# RaduProiectFinal_v18.net
KiCad netlist of a schematic drawn in EAGLE
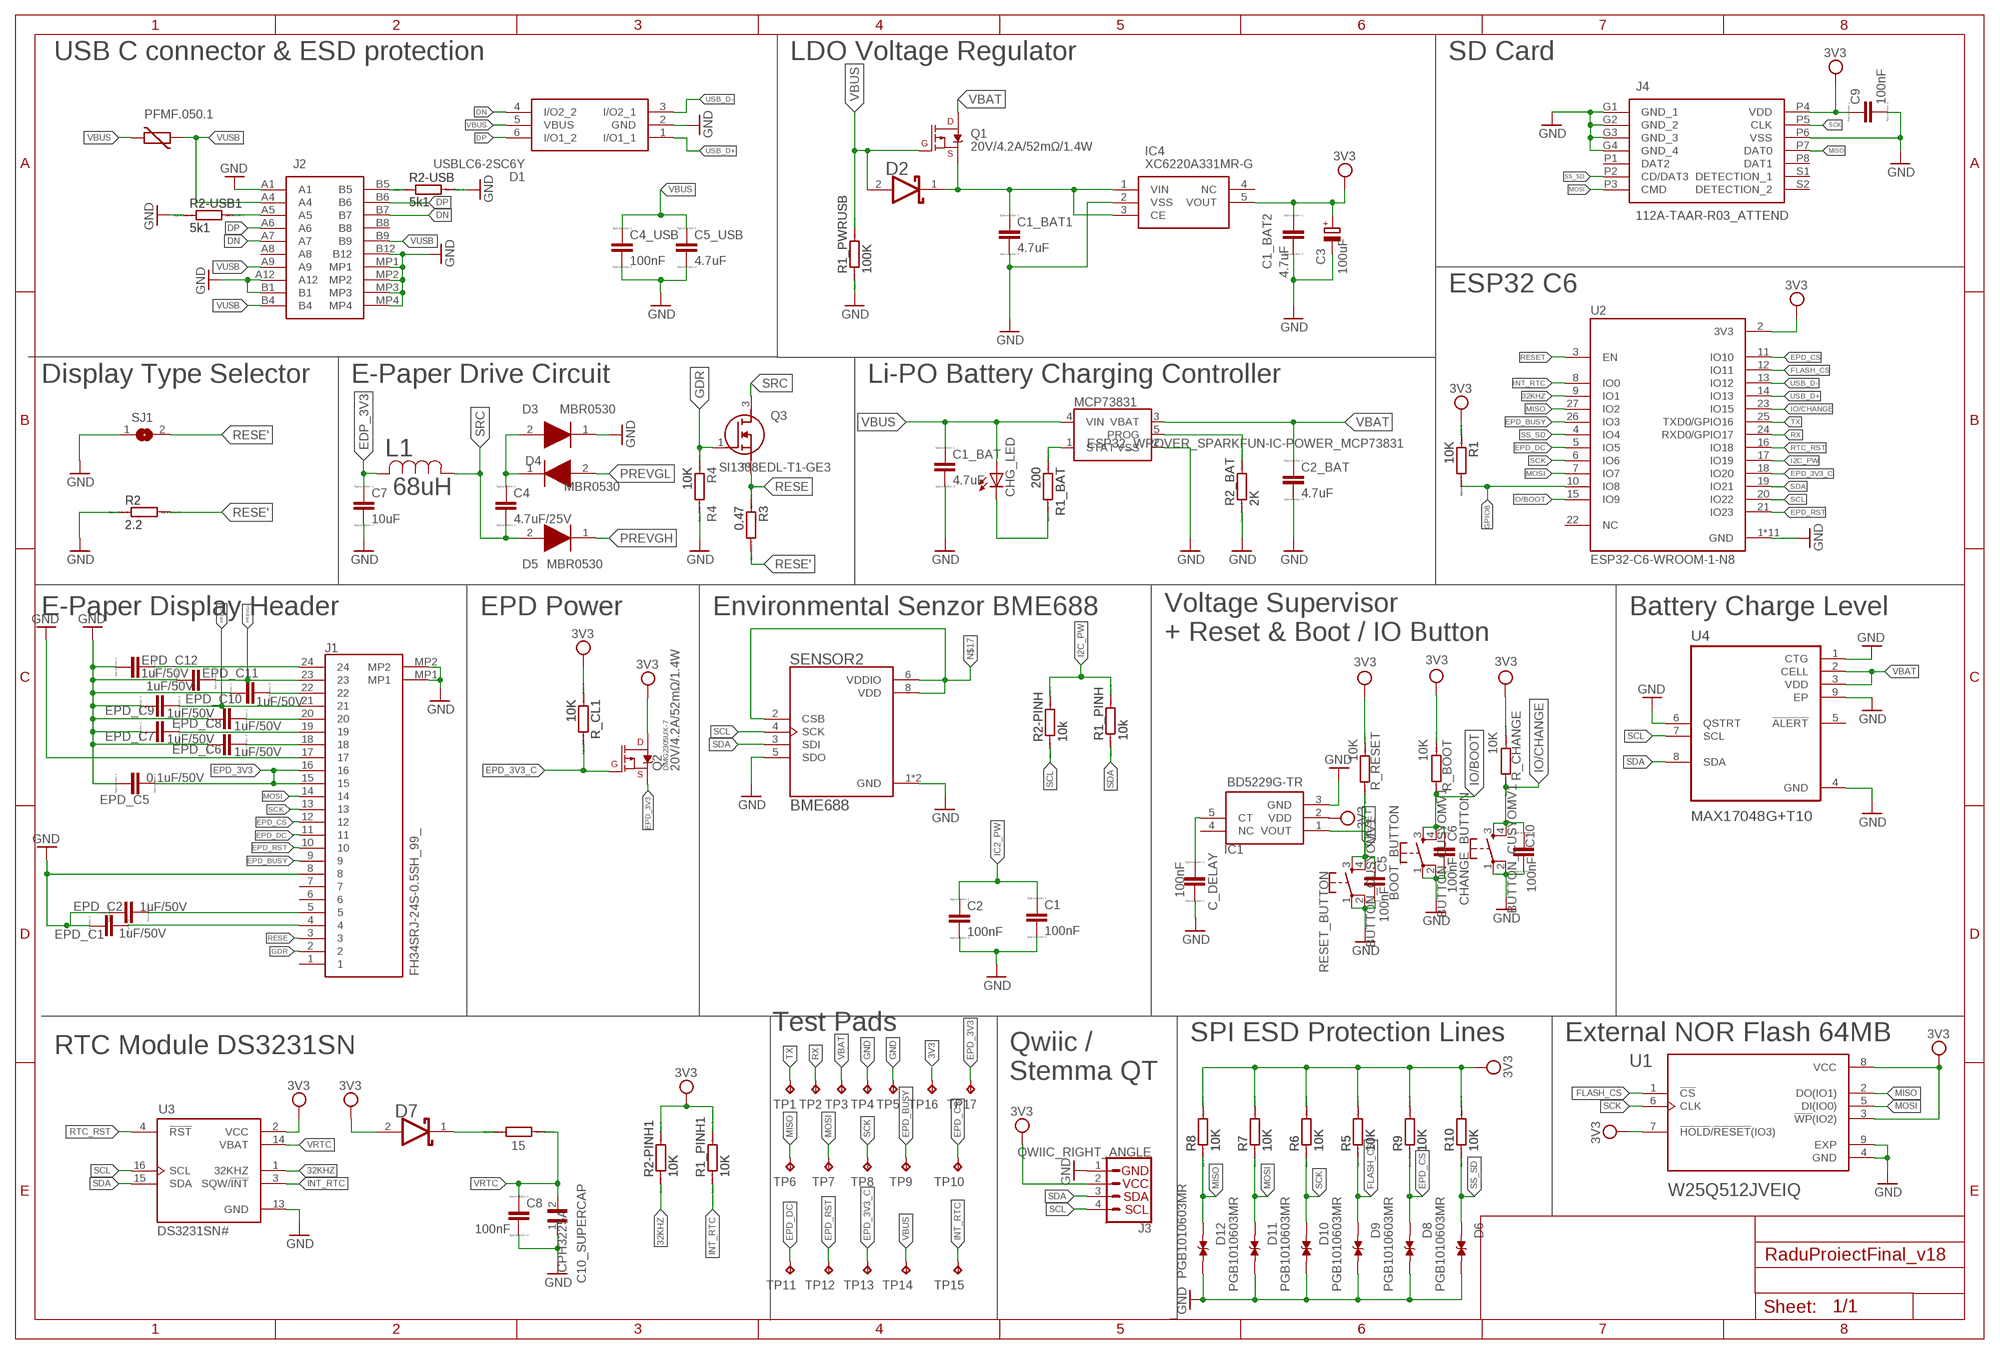
[diagram p0: schematic, sheet 1]

(export (version "E")
  (design (tool "Eeschema 10.0.6"))
  (components
    (comp (ref "BOOT_BUTTON")
      (value "BUTTON_CUSYOMV1")
      (footprint "eagle-import:MYBUTTON")
      (libsource (lib "eagle-import") (part "BUTTON_CUSYOMV1"))
    )
    (comp (ref "C1")
      (value "100nF")
      (footprint "eagle-import:ESP32_WROVER_EAGLE-LTSPICE_C0402")
      (libsource (lib "eagle-import") (part "ESP32_WROVER_EAGLE-LTSPICE_CC0402"))
    )
    (comp (ref "C1_BAT")
      (value "4.7uF")
      (footprint "eagle-import:ESP32_WROVER_EAGLE-LTSPICE_C0402")
      (libsource (lib "eagle-import") (part "ESP32_WROVER_EAGLE-LTSPICE_CC0402"))
    )
    (comp (ref "C1_BAT1")
      (value "4.7uF")
      (footprint "eagle-import:ESP32_WROVER_EAGLE-LTSPICE_C0402")
      (libsource (lib "eagle-import") (part "ESP32_WROVER_EAGLE-LTSPICE_CC0402"))
    )
    (comp (ref "C1_BAT2")
      (value "4.7uF")
      (footprint "eagle-import:ESP32_WROVER_EAGLE-LTSPICE_C0402")
      (libsource (lib "eagle-import") (part "ESP32_WROVER_EAGLE-LTSPICE_CC0402"))
    )
    (comp (ref "C2")
      (value "100nF")
      (footprint "eagle-import:ESP32_WROVER_EAGLE-LTSPICE_C0402")
      (libsource (lib "eagle-import") (part "ESP32_WROVER_EAGLE-LTSPICE_CC0402"))
    )
    (comp (ref "C2_BAT")
      (value "4.7uF")
      (footprint "eagle-import:ESP32_WROVER_EAGLE-LTSPICE_C0402")
      (libsource (lib "eagle-import") (part "ESP32_WROVER_EAGLE-LTSPICE_CC0402"))
    )
    (comp (ref "C3")
      (value "100uF")
      (footprint "eagle-import:RCL_CT3528")
      (libsource (lib "eagle-import") (part "RCL_CPOL-EUCT3528"))
    )
    (comp (ref "C4")
      (value "4.7uF/25V")
      (footprint "eagle-import:ESP32_WROVER_EAGLE-LTSPICE_C0402")
      (libsource (lib "eagle-import") (part "ESP32_WROVER_EAGLE-LTSPICE_CC0402"))
    )
    (comp (ref "C4_USB")
      (value "100nF")
      (footprint "eagle-import:ESP32_WROVER_EAGLE-LTSPICE_C0402")
      (libsource (lib "eagle-import") (part "ESP32_WROVER_EAGLE-LTSPICE_CC0402"))
    )
    (comp (ref "C5")
      (value "100nF")
      (footprint "eagle-import:EAGLE-LTSPICE_C0402")
      (libsource (lib "eagle-import") (part "EAGLE-LTSPICE_CC0402"))
    )
    (comp (ref "C5_USB")
      (value "4.7uF")
      (footprint "eagle-import:ESP32_WROVER_EAGLE-LTSPICE_C0402")
      (libsource (lib "eagle-import") (part "ESP32_WROVER_EAGLE-LTSPICE_CC0402"))
    )
    (comp (ref "C6")
      (value "100nF")
      (footprint "eagle-import:EAGLE-LTSPICE_C0402")
      (libsource (lib "eagle-import") (part "EAGLE-LTSPICE_CC0402"))
    )
    (comp (ref "C7")
      (value "10uF")
      (footprint "eagle-import:ESP32_WROVER_EAGLE-LTSPICE_C0402")
      (libsource (lib "eagle-import") (part "ESP32_WROVER_EAGLE-LTSPICE_CC0402"))
    )
    (comp (ref "C8")
      (value "100nF")
      (footprint "eagle-import:ESP32_WROVER_EAGLE-LTSPICE_C0402")
      (libsource (lib "eagle-import") (part "ESP32_WROVER_EAGLE-LTSPICE_CC0402"))
    )
    (comp (ref "C9")
      (value "100nF")
      (footprint "eagle-import:ESP32_WROVER_EAGLE-LTSPICE_C0402")
      (libsource (lib "eagle-import") (part "ESP32_WROVER_EAGLE-LTSPICE_CC0402"))
    )
    (comp (ref "C10")
      (value "100nF")
      (footprint "eagle-import:EAGLE-LTSPICE_C0402")
      (libsource (lib "eagle-import") (part "EAGLE-LTSPICE_CC0402"))
    )
    (comp (ref "C10_SUPERCAP")
      (value "CPH3225A")
      (footprint "eagle-import:CAPCP3225X100N")
      (fields (field (name "MF") "Seiko Instruments"))
      (libsource (lib "eagle-import") (part "CPH3225A"))
    )
    (comp (ref "CHANGE_BUTTON")
      (value "BUTTON_CUSYOMV1")
      (footprint "eagle-import:MYBUTTON")
      (libsource (lib "eagle-import") (part "BUTTON_CUSYOMV1"))
    )
    (comp (ref "CHG_LED")
      (value "ADAFRUIT_LEDCHIP-LED0603")
      (footprint "eagle-import:ADAFRUIT_CHIP-LED0603")
      (libsource (lib "eagle-import") (part "ADAFRUIT_LEDCHIP-LED0603"))
    )
    (comp (ref "C_DELAY")
      (value "100nF")
      (footprint "eagle-import:ESP32_WROVER_EAGLE-LTSPICE_C0402")
      (libsource (lib "eagle-import") (part "ESP32_WROVER_EAGLE-LTSPICE_CC0402"))
    )
    (comp (ref "D1")
      (value "USBLC6-2SC6Y")
      (footprint "eagle-import:SOT95P280X145-6N")
      (fields (field (name "MF") "STMicroelectronics"))
      (libsource (lib "eagle-import") (part "USBLC6-2SC6Y"))
    )
    (comp (ref "D2")
      (value "ESP32_WROVER_AVX---SD0805S020S1R0_AVX_SD0805S020S1R0_0_0AVX_SD0805S020S1R0_0_0")
      (footprint "eagle-import:ESP32_WROVER_AVX---SD0805S020S1R0_AVX_SD0805S020S1R0_0")
      (fields
        (field (name "DIGIKEY_PART_NUMBER") "478-7800-1-ND")
        (field (name "MF") "AVX")
        (field (name "MOUSER_PART_NUMBER") "581-SD0805S020S1R0")
      )
      (libsource (lib "eagle-import") (part "ESP32_WROVER_AVX---SD0805S020S1R0_AVX_SD0805S020S1R0_0_0AVX_SD0805S020S1R0_0_0"))
    )
    (comp (ref "D3")
      (value "MBR0530")
      (footprint "eagle-import:SOD3716X135N")
      (fields (field (name "MF") "ON Semiconductor"))
      (libsource (lib "eagle-import") (part "MBR0530"))
    )
    (comp (ref "D4")
      (value "MBR0530")
      (footprint "eagle-import:SOD3716X135N")
      (fields (field (name "MF") "ON Semiconductor"))
      (libsource (lib "eagle-import") (part "MBR0530"))
    )
    (comp (ref "D5")
      (value "MBR0530")
      (footprint "eagle-import:SOD3716X135N")
      (fields (field (name "MF") "ON Semiconductor"))
      (libsource (lib "eagle-import") (part "MBR0530"))
    )
    (comp (ref "D6")
      (value "PGB1010603MR")
      (footprint "eagle-import:DIOC1608X36N")
      (fields (field (name "MF") "Littelfuse Inc."))
      (libsource (lib "eagle-import") (part "PGB1010603MR"))
    )
    (comp (ref "D7")
      (value "ESP32_WROVER_AVX---SD0805S020S1R0_AVX_SD0805S020S1R0_0_0AVX_SD0805S020S1R0_0_0")
      (footprint "eagle-import:ESP32_WROVER_AVX---SD0805S020S1R0_AVX_SD0805S020S1R0_0")
      (fields
        (field (name "DIGIKEY_PART_NUMBER") "478-7800-1-ND")
        (field (name "MF") "AVX")
        (field (name "MOUSER_PART_NUMBER") "581-SD0805S020S1R0")
      )
      (libsource (lib "eagle-import") (part "ESP32_WROVER_AVX---SD0805S020S1R0_AVX_SD0805S020S1R0_0_0AVX_SD0805S020S1R0_0_0"))
    )
    (comp (ref "D8")
      (value "PGB1010603MR")
      (footprint "eagle-import:DIOC1608X36N")
      (fields (field (name "MF") "Littelfuse Inc."))
      (libsource (lib "eagle-import") (part "PGB1010603MR"))
    )
    (comp (ref "D9")
      (value "PGB1010603MR")
      (footprint "eagle-import:DIOC1608X36N")
      (fields (field (name "MF") "Littelfuse Inc."))
      (libsource (lib "eagle-import") (part "PGB1010603MR"))
    )
    (comp (ref "D10")
      (value "PGB1010603MR")
      (footprint "eagle-import:DIOC1608X36N")
      (fields (field (name "MF") "Littelfuse Inc."))
      (libsource (lib "eagle-import") (part "PGB1010603MR"))
    )
    (comp (ref "D11")
      (value "PGB1010603MR")
      (footprint "eagle-import:DIOC1608X36N")
      (fields (field (name "MF") "Littelfuse Inc."))
      (libsource (lib "eagle-import") (part "PGB1010603MR"))
    )
    (comp (ref "D12")
      (value "PGB1010603MR")
      (footprint "eagle-import:DIOC1608X36N")
      (fields (field (name "MF") "Littelfuse Inc."))
      (libsource (lib "eagle-import") (part "PGB1010603MR"))
    )
    (comp (ref "EPD_C1")
      (value "1uF/50V")
      (footprint "eagle-import:EAGLE-LTSPICE_C0402")
      (libsource (lib "eagle-import") (part "EAGLE-LTSPICE_CC0402"))
    )
    (comp (ref "EPD_C2")
      (value "1uF/50V")
      (footprint "eagle-import:EAGLE-LTSPICE_C0402")
      (libsource (lib "eagle-import") (part "EAGLE-LTSPICE_CC0402"))
    )
    (comp (ref "EPD_C5")
      (value "0.1uF/50V")
      (footprint "eagle-import:EAGLE-LTSPICE_C0402")
      (libsource (lib "eagle-import") (part "EAGLE-LTSPICE_CC0402"))
    )
    (comp (ref "EPD_C6")
      (value "1uF/50V")
      (footprint "eagle-import:EAGLE-LTSPICE_C0402")
      (libsource (lib "eagle-import") (part "EAGLE-LTSPICE_CC0402"))
    )
    (comp (ref "EPD_C7")
      (value "1uF/50V")
      (footprint "eagle-import:EAGLE-LTSPICE_C0402")
      (libsource (lib "eagle-import") (part "EAGLE-LTSPICE_CC0402"))
    )
    (comp (ref "EPD_C8")
      (value "1uF/50V")
      (footprint "eagle-import:EAGLE-LTSPICE_C0402")
      (libsource (lib "eagle-import") (part "EAGLE-LTSPICE_CC0402"))
    )
    (comp (ref "EPD_C9")
      (value "1uF/50V")
      (footprint "eagle-import:EAGLE-LTSPICE_C0402")
      (libsource (lib "eagle-import") (part "EAGLE-LTSPICE_CC0402"))
    )
    (comp (ref "EPD_C10")
      (value "1uF/50V")
      (footprint "eagle-import:EAGLE-LTSPICE_C0402")
      (libsource (lib "eagle-import") (part "EAGLE-LTSPICE_CC0402"))
    )
    (comp (ref "EPD_C11")
      (value "1uF/50V")
      (footprint "eagle-import:EAGLE-LTSPICE_C0402")
      (libsource (lib "eagle-import") (part "EAGLE-LTSPICE_CC0402"))
    )
    (comp (ref "EPD_C12")
      (value "1uF/50V")
      (footprint "eagle-import:EAGLE-LTSPICE_C0402")
      (libsource (lib "eagle-import") (part "EAGLE-LTSPICE_CC0402"))
    )
    (comp (ref "IC1")
      (value "BD5229G-TR")
      (footprint "eagle-import:SOT95P280X125-5N")
      (fields (field (name "MOUSER_PART_NUMBER") "755-BD5229G-TR"))
      (libsource (lib "eagle-import") (part "BD5229G-TR"))
    )
    (comp (ref "IC4")
      (value "XC6220A331MR-G")
      (footprint "eagle-import:SOT95P280X120-5N")
      (fields (field (name "MOUSER_PART_NUMBER") "865-XC6220A331MR-G"))
      (libsource (lib "eagle-import") (part "XC6220A331MR-G"))
    )
    (comp (ref "J1")
      (value "FH34SRJ-24S-0.5SH_99_")
      (footprint "eagle-import:FH34SRJ24S05SH99")
      (fields
        (field (name "MANUFACTURER_PART_NUMBER") "FH34SRJ-24S-0.5SH(99)")
        (field (name "MOUSER_PART_NUMBER") "798-FH34SRJ24S05SH99")
      )
      (libsource (lib "eagle-import") (part "FH34SRJ-24S-0.5SH_99_"))
    )
    (comp (ref "J2")
      (value "SAMACSYS_PARTS_USB4110-GF-A")
      (footprint "eagle-import:SAMACSYS_PARTS_USB4110GFA")
      (fields
        (field (name "MANUFACTURER_PART_NUMBER") "USB4110-GF-A")
        (field (name "MOUSER_PART_NUMBER") "640-USB4110-GF-A")
      )
      (libsource (lib "eagle-import") (part "SAMACSYS_PARTS_USB4110-GF-A"))
    )
    (comp (ref "J3")
      (value "QWIIC_RIGHT_ANGLE")
      (footprint "eagle-import:JST04_1MM_RA")
      (libsource (lib "eagle-import") (part "QWIIC_CONNECTORJS-1MM"))
    )
    (comp (ref "J4")
      (value "112A-TAAR-R03_ATTEND")
      (footprint "eagle-import:112ATAARR03ATTEND")
      (fields (field (name "MANUFACTURER_PART_NUMBER") "112A-TAAR-R03 ATTEND"))
      (libsource (lib "eagle-import") (part "112A-TAAR-R03_ATTEND"))
    )
    (comp (ref "L1")
      (value "68uH")
      (footprint "eagle-import:IND_4828-WE-TPC_WRE")
      (fields
        (field (name "MANUFACTURER_PART_NUMBER") "744043680")
        (field (name "COPYRIGHT") "Copyright (C) 2024 Ultra Librarian. All rights reserved.")
      )
      (libsource (lib "eagle-import") (part "744043680IND_4828-WE-TPC_WRE"))
    )
    (comp (ref "MCP73831")
      (value "ESP32_WROVER_SPARKFUN-IC-POWER_MCP73831")
      (footprint "eagle-import:ESP32_WROVER_SPARKFUN-IC-POWER_SOT23-5")
      (libsource (lib "eagle-import") (part "ESP32_WROVER_SPARKFUN-IC-POWER_MCP73831"))
    )
    (comp (ref "PFMF.050.1")
      (value "ESP32C6_VARISTORCN1812")
      (footprint "eagle-import:ESP32C6_VARISTOR_CT_CN1812")
      (libsource (lib "eagle-import") (part "ESP32C6_VARISTORCN1812"))
    )
    (comp (ref "Q1")
      (value "20V/4.2A/52mΩ/1.4W")
      (footprint "eagle-import:ESP32_WROVER_SPARKFUN-DISCRETESEMI_SOT23-3")
      (libsource (lib "eagle-import") (part "ESP32_WROVER_SPARKFUN-DISCRETESEMI_MOSFET_PCH-DMG2305UX-7"))
    )
    (comp (ref "Q2")
      (value "20V/4.2A/52mΩ/1.4W")
      (footprint "eagle-import:ESP32_WROVER_SPARKFUN-DISCRETESEMI_SOT23-3")
      (libsource (lib "eagle-import") (part "ESP32_WROVER_SPARKFUN-DISCRETESEMI_MOSFET_PCH-DMG2305UX-7"))
    )
    (comp (ref "Q3")
      (value "SI1308EDL-T1-GE3")
      (footprint "eagle-import:SOT65P210X110-3N")
      (fields (field (name "MF") "Vishay Siliconix"))
      (libsource (lib "eagle-import") (part "SI1308EDL-T1-GE3"))
    )
    (comp (ref "R1")
      (value "10K")
      (footprint "eagle-import:ESP32_WROVER_EAGLE-LTSPICE_R0402")
      (libsource (lib "eagle-import") (part "ESP32_WROVER_EAGLE-LTSPICE_RR0402"))
    )
    (comp (ref "R1_BAT")
      (value "200")
      (footprint "eagle-import:ESP32_WROVER_EAGLE-LTSPICE_R0402")
      (libsource (lib "eagle-import") (part "ESP32_WROVER_EAGLE-LTSPICE_RR0402"))
    )
    (comp (ref "R1_PINH")
      (value "10k")
      (footprint "eagle-import:ESP32_WROVER_EAGLE-LTSPICE_R0402")
      (libsource (lib "eagle-import") (part "ESP32_WROVER_EAGLE-LTSPICE_RR0402"))
    )
    (comp (ref "R1_PINH1")
      (value "10K")
      (footprint "eagle-import:ESP32_WROVER_EAGLE-LTSPICE_R0402")
      (libsource (lib "eagle-import") (part "ESP32_WROVER_EAGLE-LTSPICE_RR0402"))
    )
    (comp (ref "R1_PWRUSB")
      (value "100K")
      (footprint "eagle-import:ESP32_WROVER_EAGLE-LTSPICE_R0402")
      (libsource (lib "eagle-import") (part "ESP32_WROVER_EAGLE-LTSPICE_RR0402"))
    )
    (comp (ref "R2")
      (value "2.2")
      (footprint "eagle-import:ESP32_WROVER_EAGLE-LTSPICE_R0402")
      (libsource (lib "eagle-import") (part "ESP32_WROVER_EAGLE-LTSPICE_RR0402"))
    )
    (comp (ref "R2-PINH")
      (value "10k")
      (footprint "eagle-import:ESP32_WROVER_EAGLE-LTSPICE_R0402")
      (libsource (lib "eagle-import") (part "ESP32_WROVER_EAGLE-LTSPICE_RR0402"))
    )
    (comp (ref "R2-PINH1")
      (value "10K")
      (footprint "eagle-import:ESP32_WROVER_EAGLE-LTSPICE_R0402")
      (libsource (lib "eagle-import") (part "ESP32_WROVER_EAGLE-LTSPICE_RR0402"))
    )
    (comp (ref "R2-USB")
      (value "5k1")
      (footprint "eagle-import:ESP32_WROVER_EAGLE-LTSPICE_R0402")
      (libsource (lib "eagle-import") (part "ESP32_WROVER_EAGLE-LTSPICE_RR0402"))
    )
    (comp (ref "R2-USB1")
      (value "5k1")
      (footprint "eagle-import:ESP32_WROVER_EAGLE-LTSPICE_R0402")
      (libsource (lib "eagle-import") (part "ESP32_WROVER_EAGLE-LTSPICE_RR0402"))
    )
    (comp (ref "R2_BAT")
      (value "2K")
      (footprint "eagle-import:ESP32_WROVER_EAGLE-LTSPICE_R0402")
      (libsource (lib "eagle-import") (part "ESP32_WROVER_EAGLE-LTSPICE_RR0402"))
    )
    (comp (ref "R3")
      (value "0.47")
      (footprint "eagle-import:ESP32_WROVER_EAGLE-LTSPICE_R0402")
      (libsource (lib "eagle-import") (part "ESP32_WROVER_EAGLE-LTSPICE_RR0402"))
    )
    (comp (ref "R4")
      (value "10K")
      (footprint "eagle-import:ESP32_WROVER_EAGLE-LTSPICE_R0402")
      (libsource (lib "eagle-import") (part "ESP32_WROVER_EAGLE-LTSPICE_RR0402"))
    )
    (comp (ref "R5")
      (value "10K")
      (footprint "eagle-import:ESP32_WROVER_EAGLE-LTSPICE_R0402")
      (libsource (lib "eagle-import") (part "ESP32_WROVER_EAGLE-LTSPICE_RR0402"))
    )
    (comp (ref "R6")
      (value "10K")
      (footprint "eagle-import:ESP32_WROVER_EAGLE-LTSPICE_R0402")
      (libsource (lib "eagle-import") (part "ESP32_WROVER_EAGLE-LTSPICE_RR0402"))
    )
    (comp (ref "R7")
      (value "10K")
      (footprint "eagle-import:ESP32_WROVER_EAGLE-LTSPICE_R0402")
      (libsource (lib "eagle-import") (part "ESP32_WROVER_EAGLE-LTSPICE_RR0402"))
    )
    (comp (ref "R8")
      (value "10K")
      (footprint "eagle-import:ESP32_WROVER_EAGLE-LTSPICE_R0402")
      (libsource (lib "eagle-import") (part "ESP32_WROVER_EAGLE-LTSPICE_RR0402"))
    )
    (comp (ref "R9")
      (value "10K")
      (footprint "eagle-import:ESP32_WROVER_EAGLE-LTSPICE_R0402")
      (libsource (lib "eagle-import") (part "ESP32_WROVER_EAGLE-LTSPICE_RR0402"))
    )
    (comp (ref "R10")
      (value "10K")
      (footprint "eagle-import:ESP32_WROVER_EAGLE-LTSPICE_R0402")
      (libsource (lib "eagle-import") (part "ESP32_WROVER_EAGLE-LTSPICE_RR0402"))
    )
    (comp (ref "RESET_BUTTON")
      (value "BUTTON_CUSYOMV1")
      (footprint "eagle-import:MYBUTTON")
      (libsource (lib "eagle-import") (part "BUTTON_CUSYOMV1"))
    )
    (comp (ref "R_BOOT")
      (value "10K")
      (footprint "eagle-import:ESP32_WROVER_EAGLE-LTSPICE_R0402")
      (libsource (lib "eagle-import") (part "ESP32_WROVER_EAGLE-LTSPICE_RR0402"))
    )
    (comp (ref "R_CAPACITOR")
      (value "15")
      (footprint "eagle-import:ESP32_WROVER_EAGLE-LTSPICE_R0402")
      (libsource (lib "eagle-import") (part "ESP32_WROVER_EAGLE-LTSPICE_RR0402"))
    )
    (comp (ref "R_CHANGE")
      (value "10K")
      (footprint "eagle-import:ESP32_WROVER_EAGLE-LTSPICE_R0402")
      (libsource (lib "eagle-import") (part "ESP32_WROVER_EAGLE-LTSPICE_RR0402"))
    )
    (comp (ref "R_CL1")
      (value "10K")
      (footprint "eagle-import:ESP32_WROVER_EAGLE-LTSPICE_R0402")
      (libsource (lib "eagle-import") (part "ESP32_WROVER_EAGLE-LTSPICE_RR0402"))
    )
    (comp (ref "R_RESET")
      (value "10K")
      (footprint "eagle-import:ESP32_WROVER_EAGLE-LTSPICE_R0402")
      (libsource (lib "eagle-import") (part "ESP32_WROVER_EAGLE-LTSPICE_RR0402"))
    )
    (comp (ref "SENSOR2")
      (value "BME688")
      (footprint "eagle-import:ESP32_WROVER_BME680_PSON80P300X300X100-8N")
      (fields (field (name "MF") "Bosch Sensortec") (field (name "MP") "BME680"))
      (libsource (lib "eagle-import") (part "ESP32_WROVER_BME680_BME680"))
    )
    (comp (ref "SJ1") (value "SJ") (footprint "eagle-import:SJ") (libsource (lib "eagle-import") (part "SJ")))
    (comp (ref "TP1")
      (value "TPTP20R")
      (footprint "eagle-import:TP20R")
      (libsource (lib "eagle-import") (part "TPTP20R"))
    )
    (comp (ref "TP2")
      (value "TPTP20R")
      (footprint "eagle-import:TP20R")
      (libsource (lib "eagle-import") (part "TPTP20R"))
    )
    (comp (ref "TP3")
      (value "TPTP20R")
      (footprint "eagle-import:TP20R")
      (libsource (lib "eagle-import") (part "TPTP20R"))
    )
    (comp (ref "TP4")
      (value "TPTP20R")
      (footprint "eagle-import:TP20R")
      (libsource (lib "eagle-import") (part "TPTP20R"))
    )
    (comp (ref "TP5")
      (value "TPTP20R")
      (footprint "eagle-import:TP20R")
      (libsource (lib "eagle-import") (part "TPTP20R"))
    )
    (comp (ref "TP6")
      (value "TPTP20R")
      (footprint "eagle-import:TP20R")
      (libsource (lib "eagle-import") (part "TPTP20R"))
    )
    (comp (ref "TP7")
      (value "TPTP20R")
      (footprint "eagle-import:TP20R")
      (libsource (lib "eagle-import") (part "TPTP20R"))
    )
    (comp (ref "TP8")
      (value "TPTP20R")
      (footprint "eagle-import:TP20R")
      (libsource (lib "eagle-import") (part "TPTP20R"))
    )
    (comp (ref "TP9")
      (value "TPTP20R")
      (footprint "eagle-import:TP20R")
      (libsource (lib "eagle-import") (part "TPTP20R"))
    )
    (comp (ref "TP10")
      (value "TPTP20R")
      (footprint "eagle-import:TP20R")
      (libsource (lib "eagle-import") (part "TPTP20R"))
    )
    (comp (ref "TP11")
      (value "TPTP20R")
      (footprint "eagle-import:TP20R")
      (libsource (lib "eagle-import") (part "TPTP20R"))
    )
    (comp (ref "TP12")
      (value "TPTP20R")
      (footprint "eagle-import:TP20R")
      (libsource (lib "eagle-import") (part "TPTP20R"))
    )
    (comp (ref "TP13")
      (value "TPTP20R")
      (footprint "eagle-import:TP20R")
      (libsource (lib "eagle-import") (part "TPTP20R"))
    )
    (comp (ref "TP14")
      (value "TPTP20R")
      (footprint "eagle-import:TP20R")
      (libsource (lib "eagle-import") (part "TPTP20R"))
    )
    (comp (ref "TP15")
      (value "TPTP20R")
      (footprint "eagle-import:TP20R")
      (libsource (lib "eagle-import") (part "TPTP20R"))
    )
    (comp (ref "TP16")
      (value "TPTP20R")
      (footprint "eagle-import:TP20R")
      (libsource (lib "eagle-import") (part "TPTP20R"))
    )
    (comp (ref "TP17")
      (value "TPTP20R")
      (footprint "eagle-import:TP20R")
      (libsource (lib "eagle-import") (part "TPTP20R"))
    )
    (comp (ref "U1")
      (value "W25Q512JVEIQ")
      (footprint "eagle-import:SON127P600X800X80-9N")
      (fields (field (name "MF") "Winbond Electronics"))
      (libsource (lib "eagle-import") (part "W25Q512JVEIQ"))
    )
    (comp (ref "U2")
      (value "ESP32-C6-WROOM-1-N8")
      (footprint "eagle-import:XCVR_ESP32-C6-WROOM-1-N8")
      (fields (field (name "MF") "Espressif Systems"))
      (libsource (lib "eagle-import") (part "ESP32-C6-WROOM-1-N8"))
    )
    (comp (ref "U3")
      (value "DS3231SN#")
      (footprint "eagle-import:SOIC127P1032X265-16N")
      (fields (field (name "MF") "Analog Devices"))
      (libsource (lib "eagle-import") (part "DS3231SN#"))
    )
    (comp (ref "U4")
      (value "MAX17048G+T10")
      (footprint "eagle-import:SON50P200X200X80-9N")
      (fields (field (name "MF") "Analog Devices"))
      (libsource (lib "eagle-import") (part "MAX17048G+T10"))
    )
  )
  (nets
    (net (code "1") (name "3V3") (class "Default")
      (node (ref "C1_BAT2") (pin "1") (pinfunction "1_1") (pintype "passive"))
      (node (ref "C3") (pin "+") (pinfunction "+_+") (pintype "passive"))
      (node (ref "C9") (pin "1") (pinfunction "1_1") (pintype "passive"))
      (node (ref "D7") (pin "2") (pinfunction "ANODE_2") (pintype "bidirectional"))
      (node (ref "IC4") (pin "5") (pinfunction "VOUT_5") (pintype "bidirectional"))
      (node (ref "J3") (pin "2") (pinfunction "2_2") (pintype "power_in"))
      (node (ref "J4") (pin "P4") (pinfunction "VDD_P4") (pintype "bidirectional"))
      (node (ref "Q2") (pin "3") (pinfunction "D_3") (pintype "bidirectional"))
      (node (ref "R1") (pin "1") (pinfunction "1_1") (pintype "passive"))
      (node (ref "R10") (pin "2") (pinfunction "2_2") (pintype "passive"))
      (node (ref "R1_PINH1") (pin "2") (pinfunction "2_2") (pintype "passive"))
      (node (ref "R2-PINH1") (pin "2") (pinfunction "2_2") (pintype "passive"))
      (node (ref "R5") (pin "2") (pinfunction "2_2") (pintype "passive"))
      (node (ref "R6") (pin "2") (pinfunction "2_2") (pintype "passive"))
      (node (ref "R7") (pin "2") (pinfunction "2_2") (pintype "passive"))
      (node (ref "R8") (pin "2") (pinfunction "2_2") (pintype "passive"))
      (node (ref "R9") (pin "2") (pinfunction "2_2") (pintype "passive"))
      (node (ref "R_BOOT") (pin "2") (pinfunction "2_2") (pintype "passive"))
      (node (ref "R_CHANGE") (pin "2") (pinfunction "2_2") (pintype "passive"))
      (node (ref "R_CL1") (pin "1") (pinfunction "1_1") (pintype "passive"))
      (node (ref "R_RESET") (pin "2") (pinfunction "2_2") (pintype "passive"))
      (node (ref "TP16") (pin "TP") (pinfunction "TP_TP") (pintype "input"))
      (node (ref "U1") (pin "3") (pinfunction "~{WP}(IO2)_3") (pintype "bidirectional"))
      (node (ref "U1") (pin "7") (pinfunction "~{HOLD}/~{RESET}(IO3)_7") (pintype "bidirectional"))
      (node (ref "U1") (pin "8") (pinfunction "VCC_8") (pintype "power_in"))
      (node (ref "U2") (pin "2") (pinfunction "3V3_2") (pintype "power_in"))
      (node (ref "U3") (pin "2") (pinfunction "VCC_2") (pintype "power_in"))
    )
    (net (code "2") (name "32KHZ") (class "Default")
      (node (ref "R2-PINH1") (pin "1") (pinfunction "1_1") (pintype "passive"))
      (node (ref "U2") (pin "9") (pinfunction "IO1_9") (pintype "bidirectional"))
      (node (ref "U3") (pin "1") (pinfunction "32KHZ_1") (pintype "output"))
    )
    (net (code "3") (name "DN") (class "Default")
      (node (ref "D1") (pin "4") (pinfunction "I/O2_2_4") (pintype "bidirectional"))
      (node (ref "J2") (pin "A7") (pinfunction "A7_A7") (pintype "bidirectional"))
      (node (ref "J2") (pin "B7") (pinfunction "B7_B7") (pintype "bidirectional"))
    )
    (net (code "4") (name "DP") (class "Default")
      (node (ref "D1") (pin "6") (pinfunction "I/O1_2_6") (pintype "bidirectional"))
      (node (ref "J2") (pin "A6") (pinfunction "A6_A6") (pintype "bidirectional"))
      (node (ref "J2") (pin "B6") (pinfunction "B6_B6") (pintype "bidirectional"))
    )
    (net (code "5") (name "EDP_3V3") (class "Default")
      (node (ref "C7") (pin "1") (pinfunction "1_1") (pintype "passive"))
      (node (ref "L1") (pin "2") (pinfunction "2_2") (pintype "passive"))
    )
    (net (code "6") (name "EPD_3V3") (class "Default")
      (node (ref "EPD_C5") (pin "2") (pinfunction "2_2") (pintype "passive"))
      (node (ref "J1") (pin "15") (pinfunction "15_15") (pintype "bidirectional"))
      (node (ref "J1") (pin "16") (pinfunction "16_16") (pintype "bidirectional"))
      (node (ref "Q2") (pin "2") (pinfunction "S_2") (pintype "bidirectional"))
      (node (ref "TP17") (pin "TP") (pinfunction "TP_TP") (pintype "input"))
    )
    (net (code "7") (name "EPD_3V3_C") (class "Default")
      (node (ref "Q2") (pin "1") (pinfunction "G_1") (pintype "bidirectional"))
      (node (ref "R_CL1") (pin "2") (pinfunction "2_2") (pintype "passive"))
      (node (ref "TP13") (pin "TP") (pinfunction "TP_TP") (pintype "input"))
      (node (ref "U2") (pin "18") (pinfunction "IO20_18") (pintype "bidirectional"))
    )
    (net (code "8") (name "EPD_BUSY") (class "Default")
      (node (ref "J1") (pin "9") (pinfunction "9_9") (pintype "bidirectional"))
      (node (ref "TP9") (pin "TP") (pinfunction "TP_TP") (pintype "input"))
      (node (ref "U2") (pin "26") (pinfunction "IO3_26") (pintype "bidirectional"))
    )
    (net (code "9") (name "EPD_CS") (class "Default")
      (node (ref "D8") (pin "1") (pinfunction "1_1") (pintype "passive"))
      (node (ref "J1") (pin "12") (pinfunction "12_12") (pintype "bidirectional"))
      (node (ref "R9") (pin "1") (pinfunction "1_1") (pintype "passive"))
      (node (ref "TP10") (pin "TP") (pinfunction "TP_TP") (pintype "input"))
      (node (ref "U2") (pin "11") (pinfunction "IO10_11") (pintype "bidirectional"))
    )
    (net (code "10") (name "EPD_DC") (class "Default")
      (node (ref "J1") (pin "11") (pinfunction "11_11") (pintype "bidirectional"))
      (node (ref "TP11") (pin "TP") (pinfunction "TP_TP") (pintype "input"))
      (node (ref "U2") (pin "5") (pinfunction "IO5_5") (pintype "bidirectional"))
    )
    (net (code "11") (name "EPD_RST") (class "Default")
      (node (ref "J1") (pin "10") (pinfunction "10_10") (pintype "bidirectional"))
      (node (ref "TP12") (pin "TP") (pinfunction "TP_TP") (pintype "input"))
      (node (ref "U2") (pin "21") (pinfunction "IO23_21") (pintype "bidirectional"))
    )
    (net (code "12") (name "FLASH_CS") (class "Default")
      (node (ref "D9") (pin "1") (pinfunction "1_1") (pintype "passive"))
      (node (ref "R5") (pin "1") (pinfunction "1_1") (pintype "passive"))
      (node (ref "U1") (pin "1") (pinfunction "~{CS}_1") (pintype "input"))
      (node (ref "U2") (pin "12") (pinfunction "IO11_12") (pintype "bidirectional"))
    )
    (net (code "13") (name "GDR") (class "Default")
      (node (ref "J1") (pin "2") (pinfunction "2_2") (pintype "bidirectional"))
      (node (ref "Q3") (pin "1") (pinfunction "G_1") (pintype "bidirectional"))
      (node (ref "R4") (pin "1") (pinfunction "1_1") (pintype "passive"))
    )
    (net (code "14") (name "GND") (class "Default")
      (node (ref "BOOT_BUTTON") (pin "1") (pinfunction "1_1") (pintype "passive"))
      (node (ref "BOOT_BUTTON") (pin "2") (pinfunction "2_2") (pintype "passive"))
      (node (ref "C1") (pin "2") (pinfunction "2_2") (pintype "passive"))
      (node (ref "C10") (pin "2") (pinfunction "2_2") (pintype "passive"))
      (node (ref "C10_SUPERCAP") (pin "1") (pinfunction "1_1") (pintype "passive"))
      (node (ref "C1_BAT") (pin "2") (pinfunction "2_2") (pintype "passive"))
      (node (ref "C1_BAT1") (pin "2") (pinfunction "2_2") (pintype "passive"))
      (node (ref "C1_BAT2") (pin "2") (pinfunction "2_2") (pintype "passive"))
      (node (ref "C2") (pin "2") (pinfunction "2_2") (pintype "passive"))
      (node (ref "C2_BAT") (pin "2") (pinfunction "2_2") (pintype "passive"))
      (node (ref "C3") (pin "-") (pinfunction "-_-") (pintype "passive"))
      (node (ref "C4_USB") (pin "2") (pinfunction "2_2") (pintype "passive"))
      (node (ref "C5") (pin "2") (pinfunction "2_2") (pintype "passive"))
      (node (ref "C5_USB") (pin "2") (pinfunction "2_2") (pintype "passive"))
      (node (ref "C6") (pin "2") (pinfunction "2_2") (pintype "passive"))
      (node (ref "C7") (pin "2") (pinfunction "2_2") (pintype "passive"))
      (node (ref "C8") (pin "2") (pinfunction "2_2") (pintype "passive"))
      (node (ref "C9") (pin "2") (pinfunction "2_2") (pintype "passive"))
      (node (ref "CHANGE_BUTTON") (pin "1") (pinfunction "1_1") (pintype "passive"))
      (node (ref "CHANGE_BUTTON") (pin "2") (pinfunction "2_2") (pintype "passive"))
      (node (ref "C_DELAY") (pin "2") (pinfunction "2_2") (pintype "passive"))
      (node (ref "D1") (pin "2") (pinfunction "GND_2") (pintype "bidirectional"))
      (node (ref "D10") (pin "2") (pinfunction "2_2") (pintype "passive"))
      (node (ref "D11") (pin "2") (pinfunction "2_2") (pintype "passive"))
      (node (ref "D12") (pin "2") (pinfunction "2_2") (pintype "passive"))
      (node (ref "D3") (pin "1") (pinfunction "K_1") (pintype "bidirectional"))
      (node (ref "D6") (pin "2") (pinfunction "2_2") (pintype "passive"))
      (node (ref "D8") (pin "2") (pinfunction "2_2") (pintype "passive"))
      (node (ref "D9") (pin "2") (pinfunction "2_2") (pintype "passive"))
      (node (ref "EPD_C1") (pin "1") (pinfunction "1_1") (pintype "passive"))
      (node (ref "EPD_C10") (pin "1") (pinfunction "1_1") (pintype "passive"))
      (node (ref "EPD_C11") (pin "1") (pinfunction "1_1") (pintype "passive"))
      (node (ref "EPD_C12") (pin "1") (pinfunction "1_1") (pintype "passive"))
      (node (ref "EPD_C2") (pin "1") (pinfunction "1_1") (pintype "passive"))
      (node (ref "EPD_C5") (pin "1") (pinfunction "1_1") (pintype "passive"))
      (node (ref "EPD_C6") (pin "1") (pinfunction "1_1") (pintype "passive"))
      (node (ref "EPD_C7") (pin "1") (pinfunction "1_1") (pintype "passive"))
      (node (ref "EPD_C8") (pin "1") (pinfunction "1_1") (pintype "passive"))
      (node (ref "EPD_C9") (pin "1") (pinfunction "1_1") (pintype "passive"))
      (node (ref "IC1") (pin "3") (pinfunction "GND_3") (pintype "bidirectional"))
      (node (ref "IC4") (pin "2") (pinfunction "VSS_2") (pintype "bidirectional"))
      (node (ref "J1") (pin "17") (pinfunction "17_17") (pintype "bidirectional"))
      (node (ref "J1") (pin "8") (pinfunction "8_8") (pintype "bidirectional"))
      (node (ref "J1") (pin "MP1") (pinfunction "MP1_MP1") (pintype "bidirectional"))
      (node (ref "J1") (pin "MP2") (pinfunction "MP2_MP2") (pintype "bidirectional"))
      (node (ref "J2") (pin "A1") (pinfunction "A1_A1") (pintype "bidirectional"))
      (node (ref "J2") (pin "A12") (pinfunction "A12_A12") (pintype "bidirectional"))
      (node (ref "J2") (pin "B1") (pinfunction "B1_B1") (pintype "bidirectional"))
      (node (ref "J2") (pin "B12") (pinfunction "B12_B12") (pintype "bidirectional"))
      (node (ref "J2") (pin "MP1") (pinfunction "MP1_MP1") (pintype "bidirectional"))
      (node (ref "J2") (pin "MP2") (pinfunction "MP2_MP2") (pintype "bidirectional"))
      (node (ref "J2") (pin "MP3") (pinfunction "MP3_MP3") (pintype "bidirectional"))
      (node (ref "J2") (pin "MP4") (pinfunction "MP4_MP4") (pintype "bidirectional"))
      (node (ref "J3") (pin "1") (pinfunction "1_1") (pintype "power_in"))
      (node (ref "J4") (pin "G1") (pinfunction "GND_1_G1") (pintype "bidirectional"))
      (node (ref "J4") (pin "G2") (pinfunction "GND_2_G2") (pintype "bidirectional"))
      (node (ref "J4") (pin "G3") (pinfunction "GND_3_G3") (pintype "bidirectional"))
      (node (ref "J4") (pin "G4") (pinfunction "GND_4_G4") (pintype "bidirectional"))
      (node (ref "J4") (pin "P6") (pinfunction "VSS_P6") (pintype "bidirectional"))
      (node (ref "MCP73831") (pin "2") (pinfunction "VSS_2") (pintype "power_in"))
      (node (ref "R1_PWRUSB") (pin "1") (pinfunction "1_1") (pintype "passive"))
      (node (ref "R2") (pin "1") (pinfunction "1_1") (pintype "passive"))
      (node (ref "R2-USB") (pin "2") (pinfunction "2_2") (pintype "passive"))
      (node (ref "R2-USB1") (pin "1") (pinfunction "1_1") (pintype "passive"))
      (node (ref "R2_BAT") (pin "1") (pinfunction "1_1") (pintype "passive"))
      (node (ref "R4") (pin "2") (pinfunction "2_2") (pintype "passive"))
      (node (ref "RESET_BUTTON") (pin "1") (pinfunction "1_1") (pintype "passive"))
      (node (ref "RESET_BUTTON") (pin "2") (pinfunction "2_2") (pintype "passive"))
      (node (ref "SENSOR2") (pin "1") (pinfunction "GND_1") (pintype "power_in"))
      (node (ref "SENSOR2") (pin "5") (pinfunction "SDO_5") (pintype "bidirectional"))
      (node (ref "SENSOR2") (pin "7") (pinfunction "GND_7") (pintype "power_in"))
      (node (ref "SJ1") (pin "1") (pinfunction "1_1") (pintype "passive"))
      (node (ref "TP4") (pin "TP") (pinfunction "TP_TP") (pintype "input"))
      (node (ref "TP5") (pin "TP") (pinfunction "TP_TP") (pintype "input"))
      (node (ref "U1") (pin "4") (pinfunction "GND_4") (pintype "power_in"))
      (node (ref "U1") (pin "9") (pinfunction "EXP_9") (pintype "passive"))
      (node (ref "U2") (pin "1") (pinfunction "GND_1") (pintype "power_in"))
      (node (ref "U2") (pin "28") (pinfunction "GND_28") (pintype "power_in"))
      (node (ref "U2") (pin "29_1") (pinfunction "GND_29_1") (pintype "power_in"))
      (node (ref "U2") (pin "29_2") (pinfunction "GND_29_2") (pintype "power_in"))
      (node (ref "U2") (pin "29_3") (pinfunction "GND_29_3") (pintype "power_in"))
      (node (ref "U2") (pin "29_4") (pinfunction "GND_29_4") (pintype "power_in"))
      (node (ref "U2") (pin "29_5") (pinfunction "GND_29_5") (pintype "power_in"))
      (node (ref "U2") (pin "29_6") (pinfunction "GND_29_6") (pintype "power_in"))
      (node (ref "U2") (pin "29_7") (pinfunction "GND_29_7") (pintype "power_in"))
      (node (ref "U2") (pin "29_8") (pinfunction "GND_29_8") (pintype "power_in"))
      (node (ref "U2") (pin "29_9") (pinfunction "GND_29_9") (pintype "power_in"))
      (node (ref "U3") (pin "13") (pinfunction "GND_13") (pintype "power_in"))
      (node (ref "U4") (pin "1") (pinfunction "CTG_1") (pintype "power_in"))
      (node (ref "U4") (pin "4") (pinfunction "GND_4") (pintype "power_in"))
      (node (ref "U4") (pin "6") (pinfunction "QSTRT_6") (pintype "input"))
      (node (ref "U4") (pin "9") (pinfunction "EP_9") (pintype "power_in"))
    )
    (net (code "15") (name "GPIO8") (class "Default")
      (node (ref "R1") (pin "2") (pinfunction "2_2") (pintype "passive"))
      (node (ref "U2") (pin "10") (pinfunction "IO8_10") (pintype "bidirectional"))
    )
    (net (code "16") (name "I2C_PW") (class "Default")
      (node (ref "R1_PINH") (pin "2") (pinfunction "2_2") (pintype "passive"))
      (node (ref "R2-PINH") (pin "2") (pinfunction "2_2") (pintype "passive"))
      (node (ref "U2") (pin "17") (pinfunction "IO19_17") (pintype "bidirectional"))
    )
    (net (code "17") (name "IC2_PW") (class "Default")
      (node (ref "C1") (pin "1") (pinfunction "1_1") (pintype "passive"))
      (node (ref "C2") (pin "1") (pinfunction "1_1") (pintype "passive"))
    )
    (net (code "18") (name "INT_RTC") (class "Default")
      (node (ref "R1_PINH1") (pin "1") (pinfunction "1_1") (pintype "passive"))
      (node (ref "TP15") (pin "TP") (pinfunction "TP_TP") (pintype "input"))
      (node (ref "U2") (pin "8") (pinfunction "IO0_8") (pintype "bidirectional"))
      (node (ref "U3") (pin "3") (pinfunction "SQW/~{INT}_3") (pintype "output"))
    )
    (net (code "19") (name "IO{slash}BOOT") (class "Default")
      (node (ref "BOOT_BUTTON") (pin "3") (pinfunction "3_3") (pintype "passive"))
      (node (ref "BOOT_BUTTON") (pin "4") (pinfunction "4_4") (pintype "passive"))
      (node (ref "C6") (pin "1") (pinfunction "1_1") (pintype "passive"))
      (node (ref "R_BOOT") (pin "1") (pinfunction "1_1") (pintype "passive"))
      (node (ref "U2") (pin "15") (pinfunction "IO9_15") (pintype "bidirectional"))
    )
    (net (code "20") (name "IO{slash}CHANGE") (class "Default")
      (node (ref "C10") (pin "1") (pinfunction "1_1") (pintype "passive"))
      (node (ref "CHANGE_BUTTON") (pin "3") (pinfunction "3_3") (pintype "passive"))
      (node (ref "CHANGE_BUTTON") (pin "4") (pinfunction "4_4") (pintype "passive"))
      (node (ref "R_CHANGE") (pin "1") (pinfunction "1_1") (pintype "passive"))
      (node (ref "U2") (pin "23") (pinfunction "IO15_23") (pintype "bidirectional"))
    )
    (net (code "21") (name "MISO") (class "Default")
      (node (ref "D12") (pin "1") (pinfunction "1_1") (pintype "passive"))
      (node (ref "J4") (pin "P7") (pinfunction "DAT0_P7") (pintype "bidirectional"))
      (node (ref "R8") (pin "1") (pinfunction "1_1") (pintype "passive"))
      (node (ref "TP6") (pin "TP") (pinfunction "TP_TP") (pintype "input"))
      (node (ref "U1") (pin "2") (pinfunction "DO(IO1)_2") (pintype "bidirectional"))
      (node (ref "U2") (pin "27") (pinfunction "IO2_27") (pintype "bidirectional"))
    )
    (net (code "22") (name "MOSI") (class "Default")
      (node (ref "D11") (pin "1") (pinfunction "1_1") (pintype "passive"))
      (node (ref "J1") (pin "14") (pinfunction "14_14") (pintype "bidirectional"))
      (node (ref "J4") (pin "P3") (pinfunction "CMD_P3") (pintype "bidirectional"))
      (node (ref "R7") (pin "1") (pinfunction "1_1") (pintype "passive"))
      (node (ref "TP7") (pin "TP") (pinfunction "TP_TP") (pintype "input"))
      (node (ref "U1") (pin "5") (pinfunction "DI(IO0)_5") (pintype "bidirectional"))
      (node (ref "U2") (pin "7") (pinfunction "IO7_7") (pintype "bidirectional"))
    )
    (net (code "23") (name "N$17") (class "Default")
      (node (ref "SENSOR2") (pin "2") (pinfunction "CSB_2") (pintype "input"))
      (node (ref "SENSOR2") (pin "6") (pinfunction "VDDIO_6") (pintype "power_in"))
      (node (ref "SENSOR2") (pin "8") (pinfunction "VDD_8") (pintype "power_in"))
    )
    (net (code "24") (name "Net-(CHG_LED-PadC)") (class "Default")
      (node (ref "CHG_LED") (pin "C") (pinfunction "C_C") (pintype "passive"))
      (node (ref "R1_BAT") (pin "2") (pinfunction "2_2") (pintype "passive"))
    )
    (net (code "25") (name "Net-(D2-CATHODE)") (class "Default")
      (node (ref "C1_BAT1") (pin "1") (pinfunction "1_1") (pintype "passive"))
      (node (ref "D2") (pin "1") (pinfunction "CATHODE_1") (pintype "bidirectional"))
      (node (ref "IC4") (pin "1") (pinfunction "VIN_1") (pintype "bidirectional"))
      (node (ref "IC4") (pin "3") (pinfunction "CE_3") (pintype "bidirectional"))
      (node (ref "Q1") (pin "2") (pinfunction "S_2") (pintype "bidirectional"))
    )
    (net (code "26") (name "Net-(D3-A)") (class "Default")
      (node (ref "C4") (pin "1") (pinfunction "1_1") (pintype "passive"))
      (node (ref "D3") (pin "2") (pinfunction "A_2") (pintype "bidirectional"))
      (node (ref "D4") (pin "1") (pinfunction "K_1") (pintype "bidirectional"))
    )
    (net (code "27") (name "Net-(D7-CATHODE)") (class "Default")
      (node (ref "D7") (pin "1") (pinfunction "CATHODE_1") (pintype "bidirectional"))
      (node (ref "R_CAPACITOR") (pin "2") (pinfunction "2_2") (pintype "passive"))
    )
    (net (code "28") (name "Net-(EPD_C1-Pad2)") (class "Default")
      (node (ref "EPD_C1") (pin "2") (pinfunction "2_2") (pintype "passive"))
      (node (ref "J1") (pin "4") (pinfunction "4_4") (pintype "bidirectional"))
    )
    (net (code "29") (name "Net-(EPD_C2-Pad2)") (class "Default")
      (node (ref "EPD_C2") (pin "2") (pinfunction "2_2") (pintype "passive"))
      (node (ref "J1") (pin "5") (pinfunction "5_5") (pintype "bidirectional"))
    )
    (net (code "30") (name "Net-(EPD_C6-Pad2)") (class "Default")
      (node (ref "EPD_C6") (pin "2") (pinfunction "2_2") (pintype "passive"))
      (node (ref "J1") (pin "18") (pinfunction "18_18") (pintype "bidirectional"))
    )
    (net (code "31") (name "Net-(EPD_C7-Pad2)") (class "Default")
      (node (ref "EPD_C7") (pin "2") (pinfunction "2_2") (pintype "passive"))
      (node (ref "J1") (pin "19") (pinfunction "19_19") (pintype "bidirectional"))
    )
    (net (code "32") (name "Net-(EPD_C8-Pad2)") (class "Default")
      (node (ref "EPD_C8") (pin "2") (pinfunction "2_2") (pintype "passive"))
      (node (ref "J1") (pin "20") (pinfunction "20_20") (pintype "bidirectional"))
    )
    (net (code "33") (name "Net-(EPD_C10-Pad2)") (class "Default")
      (node (ref "EPD_C10") (pin "2") (pinfunction "2_2") (pintype "passive"))
      (node (ref "J1") (pin "22") (pinfunction "22_22") (pintype "bidirectional"))
    )
    (net (code "34") (name "Net-(EPD_C12-Pad2)") (class "Default")
      (node (ref "EPD_C12") (pin "2") (pinfunction "2_2") (pintype "passive"))
      (node (ref "J1") (pin "24") (pinfunction "24_24") (pintype "bidirectional"))
    )
    (net (code "35") (name "Net-(IC1-CT)") (class "Default")
      (node (ref "C_DELAY") (pin "1") (pinfunction "1_1") (pintype "passive"))
      (node (ref "IC1") (pin "5") (pinfunction "CT_5") (pintype "bidirectional"))
    )
    (net (code "36") (name "Net-(J2-PadA5)") (class "Default")
      (node (ref "J2") (pin "A5") (pinfunction "A5_A5") (pintype "bidirectional"))
      (node (ref "R2-USB1") (pin "2") (pinfunction "2_2") (pintype "passive"))
    )
    (net (code "37") (name "Net-(J2-PadB5)") (class "Default")
      (node (ref "J2") (pin "B5") (pinfunction "B5_B5") (pintype "bidirectional"))
      (node (ref "R2-USB") (pin "1") (pinfunction "1_1") (pintype "passive"))
    )
    (net (code "38") (name "Net-(MCP73831-PROG)") (class "Default")
      (node (ref "MCP73831") (pin "5") (pinfunction "PROG_5") (pintype "input"))
      (node (ref "R2_BAT") (pin "2") (pinfunction "2_2") (pintype "passive"))
    )
    (net (code "39") (name "Net-(MCP73831-STAT)") (class "Default")
      (node (ref "MCP73831") (pin "1") (pinfunction "STAT_1") (pintype "output"))
      (node (ref "R1_BAT") (pin "1") (pinfunction "1_1") (pintype "passive"))
    )
    (net (code "40") (name "PREVGH") (class "Default")
      (node (ref "D5") (pin "1") (pinfunction "K_1") (pintype "bidirectional"))
      (node (ref "EPD_C9") (pin "2") (pinfunction "2_2") (pintype "passive"))
      (node (ref "J1") (pin "21") (pinfunction "21_21") (pintype "bidirectional"))
    )
    (net (code "41") (name "PREVGL") (class "Default")
      (node (ref "D4") (pin "2") (pinfunction "A_2") (pintype "bidirectional"))
      (node (ref "EPD_C11") (pin "2") (pinfunction "2_2") (pintype "passive"))
      (node (ref "J1") (pin "23") (pinfunction "23_23") (pintype "bidirectional"))
    )
    (net (code "42") (name "RESE") (class "Default")
      (node (ref "J1") (pin "3") (pinfunction "3_3") (pintype "bidirectional"))
      (node (ref "Q3") (pin "2") (pinfunction "S_2") (pintype "bidirectional"))
      (node (ref "R3") (pin "1") (pinfunction "1_1") (pintype "passive"))
    )
    (net (code "43") (name "RESE'") (class "Default")
      (node (ref "R2") (pin "2") (pinfunction "2_2") (pintype "passive"))
      (node (ref "R3") (pin "2") (pinfunction "2_2") (pintype "passive"))
      (node (ref "SJ1") (pin "2") (pinfunction "2_2") (pintype "passive"))
    )
    (net (code "44") (name "RESET") (class "Default")
      (node (ref "C5") (pin "1") (pinfunction "1_1") (pintype "passive"))
      (node (ref "IC1") (pin "1") (pinfunction "VOUT_1") (pintype "bidirectional"))
      (node (ref "RESET_BUTTON") (pin "3") (pinfunction "3_3") (pintype "passive"))
      (node (ref "RESET_BUTTON") (pin "4") (pinfunction "4_4") (pintype "passive"))
      (node (ref "R_RESET") (pin "1") (pinfunction "1_1") (pintype "passive"))
      (node (ref "U2") (pin "3") (pinfunction "EN_3") (pintype "input"))
    )
    (net (code "45") (name "RTC_RST") (class "Default")
      (node (ref "U2") (pin "16") (pinfunction "IO18_16") (pintype "bidirectional"))
      (node (ref "U3") (pin "4") (pinfunction "~{RST}_4") (pintype "input"))
    )
    (net (code "46") (name "RX") (class "Default")
      (node (ref "TP2") (pin "TP") (pinfunction "TP_TP") (pintype "input"))
      (node (ref "U2") (pin "24") (pinfunction "RXD0/GPIO17_24") (pintype "bidirectional"))
    )
    (net (code "47") (name "SCK") (class "Default")
      (node (ref "D10") (pin "1") (pinfunction "1_1") (pintype "passive"))
      (node (ref "J1") (pin "13") (pinfunction "13_13") (pintype "bidirectional"))
      (node (ref "J4") (pin "P5") (pinfunction "CLK_P5") (pintype "bidirectional"))
      (node (ref "R6") (pin "1") (pinfunction "1_1") (pintype "passive"))
      (node (ref "TP8") (pin "TP") (pinfunction "TP_TP") (pintype "input"))
      (node (ref "U1") (pin "6") (pinfunction "CLK_6") (pintype "input"))
      (node (ref "U2") (pin "6") (pinfunction "IO6_6") (pintype "bidirectional"))
    )
    (net (code "48") (name "SCL") (class "Default")
      (node (ref "J3") (pin "4") (pinfunction "4_4") (pintype "passive"))
      (node (ref "R2-PINH") (pin "1") (pinfunction "1_1") (pintype "passive"))
      (node (ref "SENSOR2") (pin "4") (pinfunction "SCK_4") (pintype "input"))
      (node (ref "U2") (pin "20") (pinfunction "IO22_20") (pintype "bidirectional"))
      (node (ref "U3") (pin "16") (pinfunction "SCL_16") (pintype "input"))
      (node (ref "U4") (pin "7") (pinfunction "SCL_7") (pintype "input"))
    )
    (net (code "49") (name "SDA") (class "Default")
      (node (ref "J3") (pin "3") (pinfunction "3_3") (pintype "passive"))
      (node (ref "R1_PINH") (pin "1") (pinfunction "1_1") (pintype "passive"))
      (node (ref "SENSOR2") (pin "3") (pinfunction "SDI_3") (pintype "bidirectional"))
      (node (ref "U2") (pin "19") (pinfunction "IO21_19") (pintype "bidirectional"))
      (node (ref "U3") (pin "15") (pinfunction "SDA_15") (pintype "bidirectional"))
      (node (ref "U4") (pin "8") (pinfunction "SDA_8") (pintype "bidirectional"))
    )
    (net (code "50") (name "SRC") (class "Default")
      (node (ref "C4") (pin "2") (pinfunction "2_2") (pintype "passive"))
      (node (ref "D5") (pin "2") (pinfunction "A_2") (pintype "bidirectional"))
      (node (ref "L1") (pin "1") (pinfunction "1_1") (pintype "passive"))
      (node (ref "Q3") (pin "3") (pinfunction "D_3") (pintype "bidirectional"))
    )
    (net (code "51") (name "SS_SD") (class "Default")
      (node (ref "D6") (pin "1") (pinfunction "1_1") (pintype "passive"))
      (node (ref "J4") (pin "P2") (pinfunction "CD/DAT3_P2") (pintype "bidirectional"))
      (node (ref "R10") (pin "1") (pinfunction "1_1") (pintype "passive"))
      (node (ref "U2") (pin "4") (pinfunction "IO4_4") (pintype "bidirectional"))
    )
    (net (code "52") (name "TX") (class "Default")
      (node (ref "TP1") (pin "TP") (pinfunction "TP_TP") (pintype "input"))
      (node (ref "U2") (pin "25") (pinfunction "TXD0/GPIO16_25") (pintype "bidirectional"))
    )
    (net (code "53") (name "USB_D+") (class "Default")
      (node (ref "D1") (pin "1") (pinfunction "I/O1_1_1") (pintype "bidirectional"))
      (node (ref "U2") (pin "14") (pinfunction "IO13_14") (pintype "bidirectional"))
    )
    (net (code "54") (name "USB_D-") (class "Default")
      (node (ref "D1") (pin "3") (pinfunction "I/O2_1_3") (pintype "bidirectional"))
      (node (ref "U2") (pin "13") (pinfunction "IO12_13") (pintype "bidirectional"))
    )
    (net (code "55") (name "VBAT") (class "Default")
      (node (ref "C2_BAT") (pin "1") (pinfunction "1_1") (pintype "passive"))
      (node (ref "MCP73831") (pin "3") (pinfunction "VBAT_3") (pintype "power_in"))
      (node (ref "Q1") (pin "3") (pinfunction "D_3") (pintype "bidirectional"))
      (node (ref "TP3") (pin "TP") (pinfunction "TP_TP") (pintype "input"))
      (node (ref "U4") (pin "2") (pinfunction "CELL_2") (pintype "power_in"))
      (node (ref "U4") (pin "3") (pinfunction "VDD_3") (pintype "power_in"))
    )
    (net (code "56") (name "VBUS") (class "Default")
      (node (ref "C1_BAT") (pin "1") (pinfunction "1_1") (pintype "passive"))
      (node (ref "C4_USB") (pin "1") (pinfunction "1_1") (pintype "passive"))
      (node (ref "C5_USB") (pin "1") (pinfunction "1_1") (pintype "passive"))
      (node (ref "CHG_LED") (pin "A") (pinfunction "A_A") (pintype "passive"))
      (node (ref "D1") (pin "5") (pinfunction "VBUS_5") (pintype "bidirectional"))
      (node (ref "D2") (pin "2") (pinfunction "ANODE_2") (pintype "bidirectional"))
      (node (ref "MCP73831") (pin "4") (pinfunction "VIN_4") (pintype "power_in"))
      (node (ref "PFMF.050.1") (pin "2") (pinfunction "2_2") (pintype "passive"))
      (node (ref "Q1") (pin "1") (pinfunction "G_1") (pintype "bidirectional"))
      (node (ref "R1_PWRUSB") (pin "2") (pinfunction "2_2") (pintype "passive"))
      (node (ref "TP14") (pin "TP") (pinfunction "TP_TP") (pintype "input"))
    )
    (net (code "57") (name "VRTC") (class "Default")
      (node (ref "C10_SUPERCAP") (pin "2") (pinfunction "2_2") (pintype "passive"))
      (node (ref "C8") (pin "1") (pinfunction "1_1") (pintype "passive"))
      (node (ref "R_CAPACITOR") (pin "1") (pinfunction "1_1") (pintype "passive"))
      (node (ref "U3") (pin "14") (pinfunction "VBAT_14") (pintype "power_in"))
    )
    (net (code "58") (name "VUSB") (class "Default")
      (node (ref "J2") (pin "A4") (pinfunction "A4_A4") (pintype "bidirectional"))
      (node (ref "J2") (pin "A9") (pinfunction "A9_A9") (pintype "bidirectional"))
      (node (ref "J2") (pin "B4") (pinfunction "B4_B4") (pintype "bidirectional"))
      (node (ref "J2") (pin "B9") (pinfunction "B9_B9") (pintype "bidirectional"))
      (node (ref "PFMF.050.1") (pin "1") (pinfunction "1_1") (pintype "passive"))
    )
    (net (code "59") (name "unconnected-(IC1-NC-Pad4)") (class "Default")
      (node (ref "IC1") (pin "4") (pinfunction "NC_4") (pintype "no_connect"))
    )
    (net (code "60") (name "unconnected-(IC1-VDD-Pad2)") (class "Default")
      (node (ref "IC1") (pin "2") (pinfunction "VDD_2") (pintype "bidirectional"))
    )
    (net (code "61") (name "unconnected-(IC4-NC-Pad4)") (class "Default")
      (node (ref "IC4") (pin "4") (pinfunction "NC_4") (pintype "no_connect"))
    )
    (net (code "62") (name "unconnected-(J1-Pad1)") (class "Default")
      (node (ref "J1") (pin "1") (pinfunction "1_1") (pintype "bidirectional"))
    )
    (net (code "63") (name "unconnected-(J1-Pad6)") (class "Default")
      (node (ref "J1") (pin "6") (pinfunction "6_6") (pintype "bidirectional"))
    )
    (net (code "64") (name "unconnected-(J1-Pad7)") (class "Default")
      (node (ref "J1") (pin "7") (pinfunction "7_7") (pintype "bidirectional"))
    )
    (net (code "65") (name "unconnected-(J2-PadA8)") (class "Default")
      (node (ref "J2") (pin "A8") (pinfunction "A8_A8") (pintype "bidirectional"))
    )
    (net (code "66") (name "unconnected-(J2-PadB8)") (class "Default")
      (node (ref "J2") (pin "B8") (pinfunction "B8_B8") (pintype "bidirectional"))
    )
    (net (code "67") (name "unconnected-(J4-DAT1-PadP8)") (class "Default")
      (node (ref "J4") (pin "P8") (pinfunction "DAT1_P8") (pintype "bidirectional"))
    )
    (net (code "68") (name "unconnected-(J4-DAT2-PadP1)") (class "Default")
      (node (ref "J4") (pin "P1") (pinfunction "DAT2_P1") (pintype "bidirectional"))
    )
    (net (code "69") (name "unconnected-(J4-DETECTION_1-PadS1)") (class "Default")
      (node (ref "J4") (pin "S1") (pinfunction "DETECTION_1_S1") (pintype "bidirectional"))
    )
    (net (code "70") (name "unconnected-(J4-DETECTION_2-PadS2)") (class "Default")
      (node (ref "J4") (pin "S2") (pinfunction "DETECTION_2_S2") (pintype "bidirectional"))
    )
    (net (code "71") (name "unconnected-(U2-NC-Pad22)") (class "Default")
      (node (ref "U2") (pin "22") (pinfunction "NC_22") (pintype "no_connect"))
    )
    (net (code "72") (name "unconnected-(U4-~{ALERT}-Pad5)") (class "Default")
      (node (ref "U4") (pin "5") (pinfunction "~{ALERT}_5") (pintype "output"))
    )
  )
)
